# Saw_VCO.net
KiCad netlist of a schematic drawn in Altium Designer
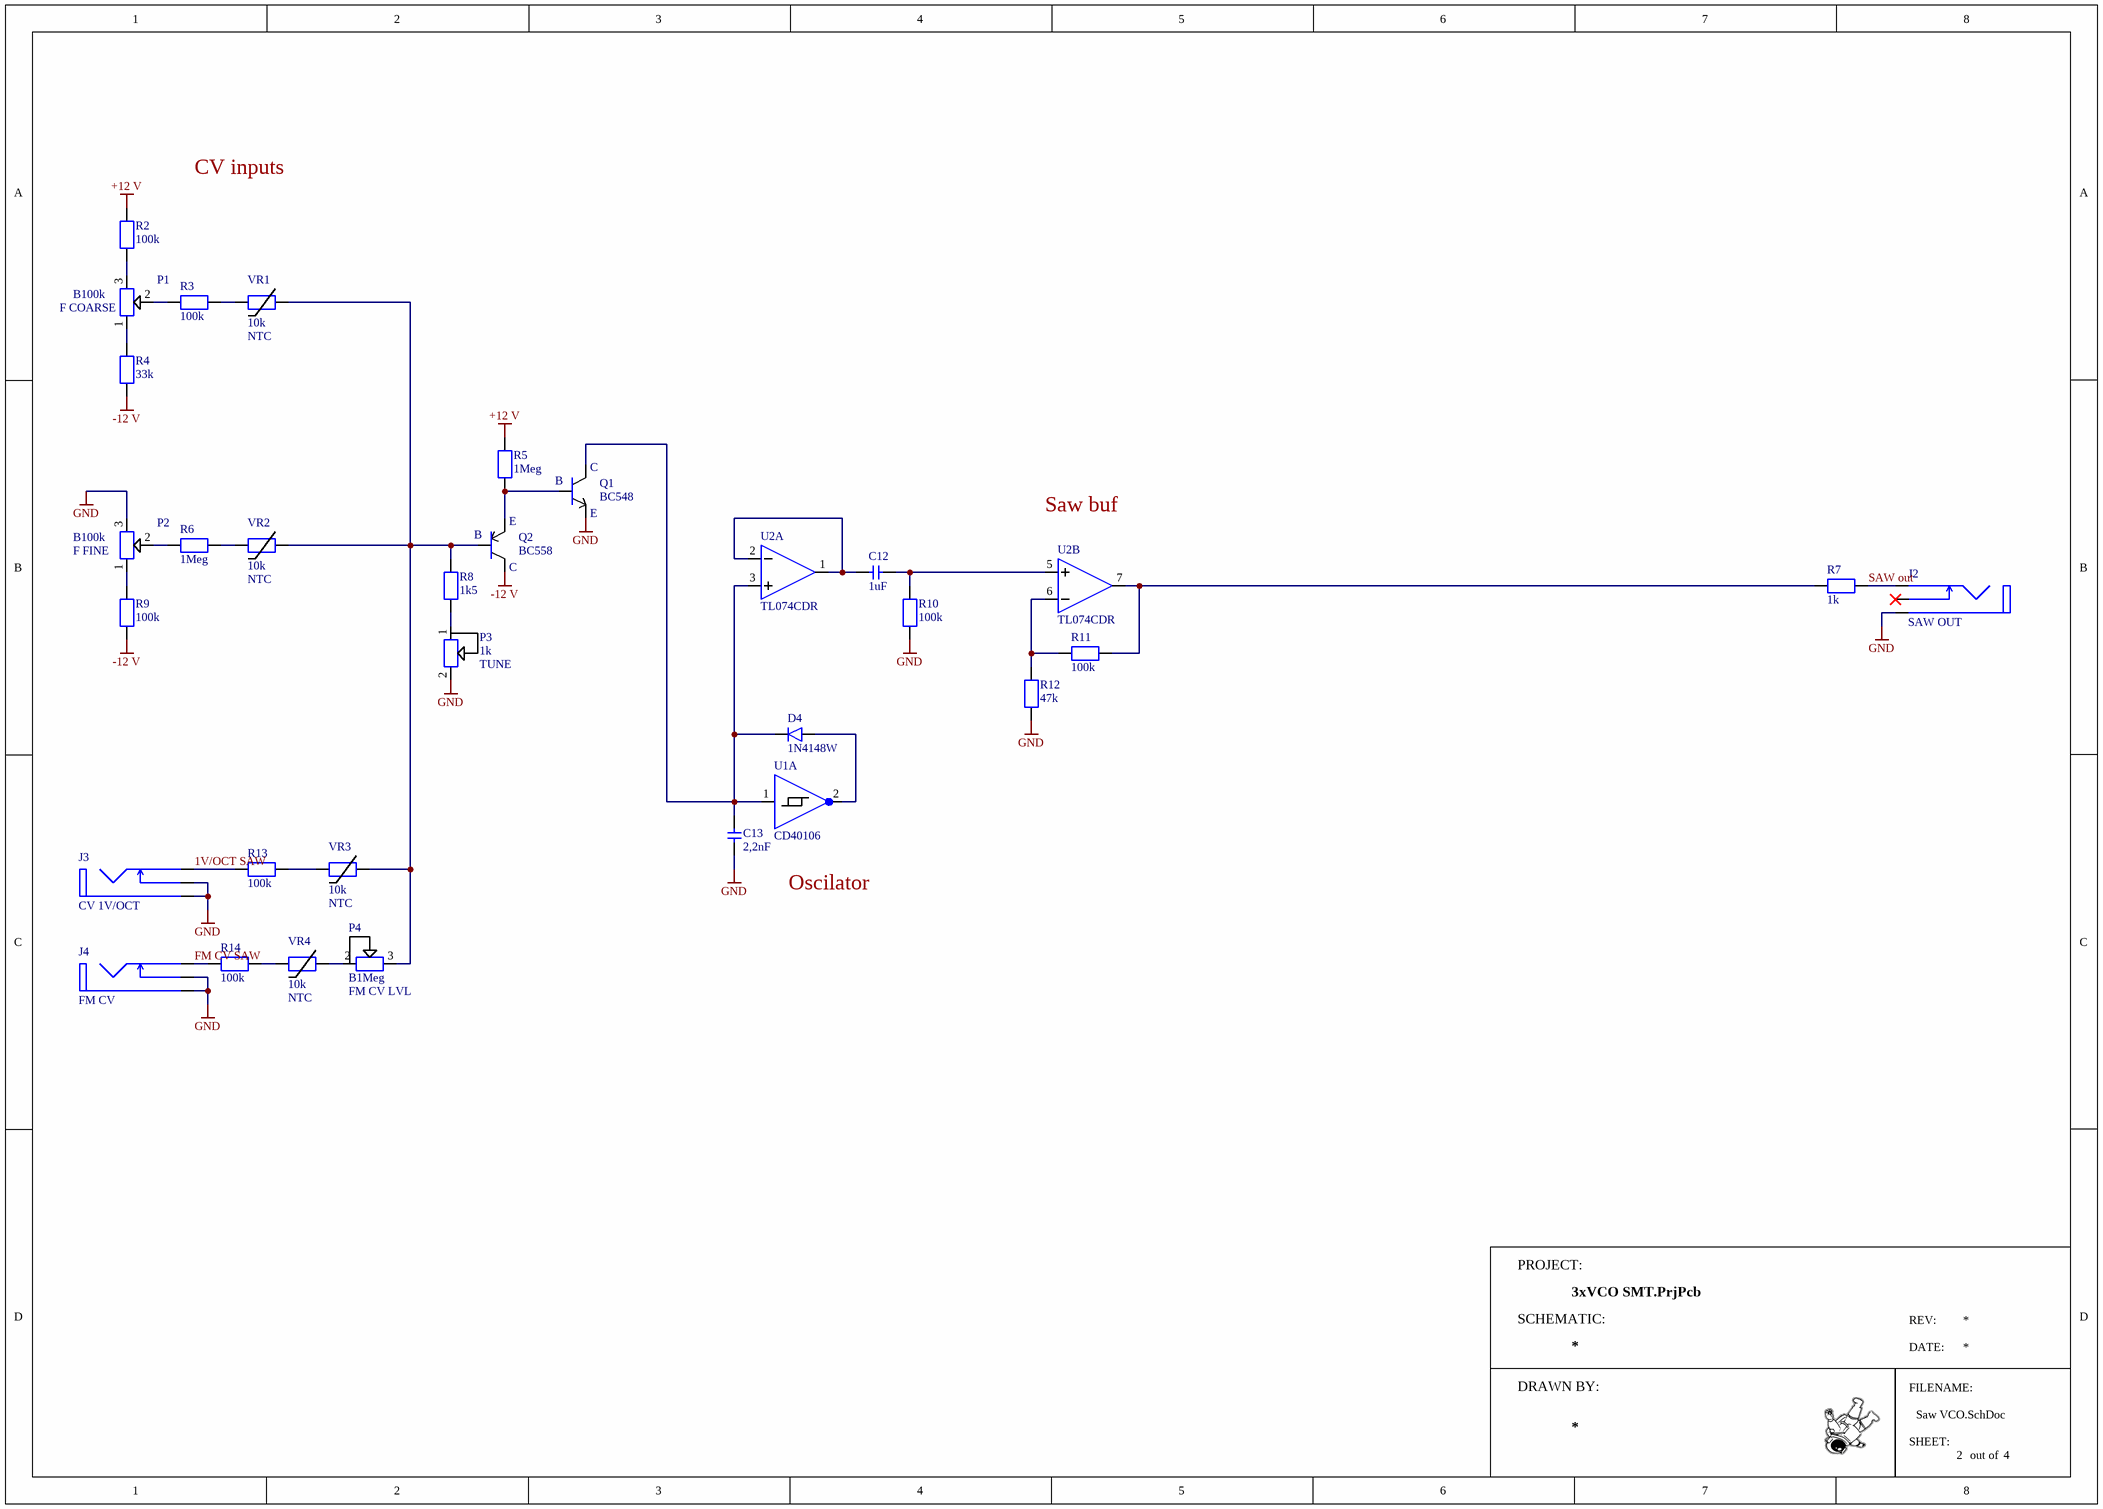
[diagram p0: Saw VCO.SchDoc]

(export (version "E")
  (design (tool "Eeschema 10.0.6"))
  (components
    (comp (ref "C12")
      (value "1uF")
      (footprint "Cap SMD 0805")
      (description "SMD Capacitor Non-Polarised 0805 Package")
      (fields (field (name "Comment") "CAP"))
      (libsource (lib "Generic components") (part "Capacitor SMD 0805"))
    )
    (comp (ref "C13")
      (value "2,2nF")
      (footprint "Cap SMD 0805")
      (description "SMD Capacitor Non-Polarised 0805 Package")
      (fields (field (name "Comment") "CAP"))
      (libsource (lib "Generic components") (part "Capacitor SMD 0805"))
    )
    (comp (ref "D4")
      (value "DIODE")
      (footprint "SOD-123")
      (description "Generic SMD Diode SOD123 Package")
      (fields (field (name "MODEL") "1N4148W"))
      (libsource (lib "Diodes") (part "Diode SMD SOD123"))
    )
    (comp (ref "J2")
      (value "JACK Mono")
      (footprint "PJ301M")
      (description "PJ301M Eurorack 3,5 mm Patch Socket PCB Mount")
      (fields (field (name "LABEL") "SAW OUT"))
      (libsource (lib "Connectors") (part "PJ301M"))
    )
    (comp (ref "J3")
      (value "JACK Mono")
      (footprint "PJ301M")
      (description "PJ301M Eurorack 3,5 mm Patch Socket PCB Mount")
      (fields (field (name "LABEL") "CV 1V/OCT"))
      (libsource (lib "Connectors") (part "PJ301M"))
    )
    (comp (ref "J4")
      (value "JACK Mono")
      (footprint "PJ301M")
      (description "PJ301M Eurorack 3,5 mm Patch Socket PCB Mount")
      (fields (field (name "LABEL") "FM CV"))
      (libsource (lib "Connectors") (part "PJ301M"))
    )
    (comp (ref "P1")
      (value "B100k")
      (footprint "9 mm PCB Potentiometer")
      (description "PCB Mount 9mm Mono Potentiometer THT")
      (fields (field (name "PARAMETER") "F COARSE") (field (name "Comment") "Mono Pot"))
      (libsource (lib "Potentiometers") (part "Potentiometer 9 mm"))
    )
    (comp (ref "P2")
      (value "B100k")
      (footprint "9 mm PCB Potentiometer")
      (description "PCB Mount 9mm Mono Potentiometer THT")
      (fields (field (name "PARAMETER") "F FINE") (field (name "Comment") "Mono Pot"))
      (libsource (lib "Potentiometers") (part "Potentiometer 9 mm"))
    )
    (comp (ref "P3")
      (value "1k")
      (footprint "Multiturn Potentiometer inline")
      (description "PCB Mount Multiturn Trimmer Potentiometer Top Adjustable as Variable Resistor Clockwise Increase")
      (fields (field (name "PARAMETER") "TUNE") (field (name "Comment") "VR"))
      (libsource (lib "Potentiometers") (part "VR A Multiturn THT"))
    )
    (comp (ref "P4")
      (value "B1Meg")
      (footprint "9 mm PCB Potentiometer")
      (description "PCB Mount 9mm Mono Potentiometer THT as Variable Resistor Clockwise Decrease")
      (fields (field (name "PARAMETER") "FM CV LVL") (field (name "Comment") "VR"))
      (libsource (lib "Potentiometers") (part "VR B 9 mm"))
    )
    (comp (ref "Q1")
      (value "BC548")
      (footprint "TO-92 wide")
      (description "BC548 NPN Transistor THT TO-92 Package")
      (libsource (lib "Transistors") (part "BC548"))
    )
    (comp (ref "Q2")
      (value "BC558")
      (footprint "TO-92 wide")
      (description "BC558 PNP Transistor THT TO-92 Package")
      (libsource (lib "Transistors") (part "BC558"))
    )
    (comp (ref "R2")
      (value "100k")
      (footprint "Resistor SMD 0805")
      (description "SMD Resistor 0805 package")
      (fields (field (name "Comment") "RES"))
      (libsource (lib "Generic components") (part "Resistor SMD 0805"))
    )
    (comp (ref "R3")
      (value "100k")
      (footprint "Resistor SMD 0805")
      (description "SMD Resistor 0805 package")
      (fields (field (name "Comment") "RES"))
      (libsource (lib "Generic components") (part "Resistor SMD 0805"))
    )
    (comp (ref "R4")
      (value "33k")
      (footprint "Resistor SMD 0805")
      (description "SMD Resistor 0805 package")
      (fields (field (name "Comment") "RES"))
      (libsource (lib "Generic components") (part "Resistor SMD 0805"))
    )
    (comp (ref "R5")
      (value "1Meg")
      (footprint "Resistor SMD 0805")
      (description "SMD Resistor 0805 package")
      (fields (field (name "Comment") "RES"))
      (libsource (lib "Generic components") (part "Resistor SMD 0805"))
    )
    (comp (ref "R6")
      (value "1Meg")
      (footprint "Resistor SMD 0805")
      (description "SMD Resistor 0805 package")
      (fields (field (name "Comment") "RES"))
      (libsource (lib "Generic components") (part "Resistor SMD 0805"))
    )
    (comp (ref "R7")
      (value "1k")
      (footprint "Resistor SMD 0805")
      (description "SMD Resistor 0805 package")
      (fields (field (name "Comment") "RES"))
      (libsource (lib "Generic components") (part "Resistor SMD 0805"))
    )
    (comp (ref "R8")
      (value "1k5")
      (footprint "Resistor SMD 0805")
      (description "SMD Resistor 0805 package")
      (fields (field (name "Comment") "RES"))
      (libsource (lib "Generic components") (part "Resistor SMD 0805"))
    )
    (comp (ref "R9")
      (value "100k")
      (footprint "Resistor SMD 0805")
      (description "SMD Resistor 0805 package")
      (fields (field (name "Comment") "RES"))
      (libsource (lib "Generic components") (part "Resistor SMD 0805"))
    )
    (comp (ref "R10")
      (value "100k")
      (footprint "Resistor SMD 0805")
      (description "SMD Resistor 0805 package")
      (fields (field (name "Comment") "RES"))
      (libsource (lib "Generic components") (part "Resistor SMD 0805"))
    )
    (comp (ref "R11")
      (value "100k")
      (footprint "Resistor SMD 0805")
      (description "SMD Resistor 0805 package")
      (fields (field (name "Comment") "RES"))
      (libsource (lib "Generic components") (part "Resistor SMD 0805"))
    )
    (comp (ref "R12")
      (value "47k")
      (footprint "Resistor SMD 0805")
      (description "SMD Resistor 0805 package")
      (fields (field (name "Comment") "RES"))
      (libsource (lib "Generic components") (part "Resistor SMD 0805"))
    )
    (comp (ref "R13")
      (value "100k")
      (footprint "Resistor SMD 0805")
      (description "SMD Resistor 0805 package")
      (fields (field (name "Comment") "RES"))
      (libsource (lib "Generic components") (part "Resistor SMD 0805"))
    )
    (comp (ref "R14")
      (value "100k")
      (footprint "Resistor SMD 0805")
      (description "SMD Resistor 0805 package")
      (fields (field (name "Comment") "RES"))
      (libsource (lib "Generic components") (part "Resistor SMD 0805"))
    )
    (comp (ref "U1")
      (value "CD40106")
      (footprint "DIP-14 socket")
      (description "CD40106 Hex Schmitt Trigger Inverter DIP-14 Package")
      (libsource (lib "ICs") (part "CD40106 DIP-14"))
    )
    (comp (ref "U2")
      (value "TL074CDR")
      (footprint "SOIC14")
      (description "TL074CDR Quad Op-Amp SOIC14 Package")
      (libsource (lib "") (part "TL074CDR SOIC14_1"))
    )
    (comp (ref "VR1")
      (value "NTC")
      (footprint "Thermistor SMD 0805")
      (description "SMD NTC Thermistor 0805 package")
      (fields (field (name "ALTIUM_VALUE") "10k"))
      (libsource (lib "Generic components") (part "Thermistor NTC SMD 0805"))
    )
    (comp (ref "VR2")
      (value "NTC")
      (footprint "Thermistor SMD 0805")
      (description "SMD NTC Thermistor 0805 package")
      (fields (field (name "ALTIUM_VALUE") "10k"))
      (libsource (lib "Generic components") (part "Thermistor NTC SMD 0805"))
    )
    (comp (ref "VR3")
      (value "NTC")
      (footprint "Thermistor SMD 0805")
      (description "SMD NTC Thermistor 0805 package")
      (fields (field (name "ALTIUM_VALUE") "10k"))
      (libsource (lib "Generic components") (part "Thermistor NTC SMD 0805"))
    )
    (comp (ref "VR4")
      (value "NTC")
      (footprint "Thermistor SMD 0805")
      (description "SMD NTC Thermistor 0805 package")
      (fields (field (name "ALTIUM_VALUE") "10k"))
      (libsource (lib "Generic components") (part "Thermistor NTC SMD 0805"))
    )
  )
  (nets
    (net (code "1") (name "+12 V") (class "Default")
      (node (ref "R2") (pin "2") (pintype "passive"))
      (node (ref "R5") (pin "1") (pintype "passive"))
    )
    (net (code "2") (name "-12 V") (class "Default")
      (node (ref "Q2") (pin "1") (pintype "passive"))
      (node (ref "R4") (pin "1") (pintype "passive"))
      (node (ref "R9") (pin "1") (pintype "passive"))
    )
    (net (code "3") (name "/1V{slash}OCT SAW") (class "Default")
      (node (ref "J3") (pin "3") (pintype "passive"))
      (node (ref "R13") (pin "2") (pintype "passive"))
    )
    (net (code "4") (name "/FM CV SAW") (class "Default")
      (node (ref "J4") (pin "3") (pintype "passive"))
      (node (ref "R14") (pin "2") (pintype "passive"))
    )
    (net (code "5") (name "/SAW out") (class "Default")
      (node (ref "J2") (pin "3") (pintype "passive"))
      (node (ref "R7") (pin "2") (pintype "passive"))
    )
    (net (code "6") (name "GND") (class "Default")
      (node (ref "C13") (pin "1") (pintype "passive"))
      (node (ref "J2") (pin "1") (pintype "passive"))
      (node (ref "J3") (pin "1") (pintype "passive"))
      (node (ref "J3") (pin "2") (pintype "passive"))
      (node (ref "J4") (pin "1") (pintype "passive"))
      (node (ref "J4") (pin "2") (pintype "passive"))
      (node (ref "P2") (pin "3") (pintype "passive"))
      (node (ref "P3") (pin "2") (pintype "passive"))
      (node (ref "Q1") (pin "3") (pintype "passive"))
      (node (ref "R10") (pin "2") (pintype "passive"))
      (node (ref "R12") (pin "2") (pintype "passive"))
    )
    (net (code "7") (name "Net-(C12-Pad1)") (class "Default")
      (node (ref "C12") (pin "1") (pintype "passive"))
      (node (ref "R10") (pin "1") (pintype "passive"))
      (node (ref "U2") (pin "5") (pintype "passive"))
    )
    (net (code "8") (name "Net-(C12-Pad2)") (class "Default")
      (node (ref "C12") (pin "2") (pintype "passive"))
      (node (ref "U2") (pin "1") (pintype "passive"))
      (node (ref "U2") (pin "2") (pintype "passive"))
    )
    (net (code "9") (name "Net-(C13-Pad2)") (class "Default")
      (node (ref "C13") (pin "2") (pintype "passive"))
      (node (ref "D4") (pin "2") (pintype "passive"))
      (node (ref "Q1") (pin "1") (pintype "passive"))
      (node (ref "U1") (pin "1") (pintype "passive"))
      (node (ref "U2") (pin "3") (pintype "passive"))
    )
    (net (code "10") (name "Net-(D4-Pad1)") (class "Default")
      (node (ref "D4") (pin "1") (pintype "passive"))
      (node (ref "U1") (pin "2") (pintype "passive"))
    )
    (net (code "11") (name "Net-(P1-Pad1)") (class "Default")
      (node (ref "P1") (pin "1") (pintype "passive"))
      (node (ref "R4") (pin "2") (pintype "passive"))
    )
    (net (code "12") (name "Net-(P1-Pad2)") (class "Default")
      (node (ref "P1") (pin "2") (pintype "passive"))
      (node (ref "R3") (pin "2") (pintype "passive"))
    )
    (net (code "13") (name "Net-(P1-Pad3)") (class "Default")
      (node (ref "P1") (pin "3") (pintype "passive"))
      (node (ref "R2") (pin "1") (pintype "passive"))
    )
    (net (code "14") (name "Net-(P2-Pad1)") (class "Default")
      (node (ref "P2") (pin "1") (pintype "passive"))
      (node (ref "R9") (pin "2") (pintype "passive"))
    )
    (net (code "15") (name "Net-(P2-Pad2)") (class "Default")
      (node (ref "P2") (pin "2") (pintype "passive"))
      (node (ref "R6") (pin "2") (pintype "passive"))
    )
    (net (code "16") (name "Net-(P3-Pad1)") (class "Default")
      (node (ref "P3") (pin "1") (pintype "passive"))
      (node (ref "R8") (pin "2") (pintype "passive"))
    )
    (net (code "17") (name "Net-(P4-Pad2)") (class "Default")
      (node (ref "P4") (pin "2") (pintype "passive"))
      (node (ref "VR4") (pin "2") (pintype "passive"))
    )
    (net (code "18") (name "Net-(P4-Pad3)") (class "Default")
      (node (ref "P4") (pin "3") (pintype "passive"))
      (node (ref "Q2") (pin "2") (pintype "passive"))
      (node (ref "R8") (pin "1") (pintype "passive"))
      (node (ref "VR1") (pin "2") (pintype "passive"))
      (node (ref "VR2") (pin "2") (pintype "passive"))
      (node (ref "VR3") (pin "2") (pintype "passive"))
    )
    (net (code "19") (name "Net-(Q1-Pad2)") (class "Default")
      (node (ref "Q1") (pin "2") (pintype "passive"))
      (node (ref "Q2") (pin "3") (pintype "passive"))
      (node (ref "R5") (pin "2") (pintype "passive"))
    )
    (net (code "20") (name "Net-(R3-Pad1)") (class "Default")
      (node (ref "R3") (pin "1") (pintype "passive"))
      (node (ref "VR1") (pin "1") (pintype "passive"))
    )
    (net (code "21") (name "Net-(R6-Pad1)") (class "Default")
      (node (ref "R6") (pin "1") (pintype "passive"))
      (node (ref "VR2") (pin "1") (pintype "passive"))
    )
    (net (code "22") (name "Net-(R11-Pad1)") (class "Default")
      (node (ref "R11") (pin "1") (pintype "passive"))
      (node (ref "R12") (pin "1") (pintype "passive"))
      (node (ref "U2") (pin "6") (pintype "passive"))
    )
    (net (code "23") (name "Net-(R11-Pad2)") (class "Default")
      (node (ref "R11") (pin "2") (pintype "passive"))
      (node (ref "R7") (pin "1") (pintype "passive"))
      (node (ref "U2") (pin "7") (pintype "passive"))
    )
    (net (code "24") (name "Net-(R13-Pad1)") (class "Default")
      (node (ref "R13") (pin "1") (pintype "passive"))
      (node (ref "VR3") (pin "1") (pintype "passive"))
    )
    (net (code "25") (name "Net-(R14-Pad1)") (class "Default")
      (node (ref "R14") (pin "1") (pintype "passive"))
      (node (ref "VR4") (pin "1") (pintype "passive"))
    )
    (net (code "26") (name "unconnected-(J2-Pad2)") (class "Default")
      (node (ref "J2") (pin "2") (pintype "passive+no_connect"))
    )
  )
)
